# digital-psu.net
KiCad netlist of a schematic drawn in EAGLE
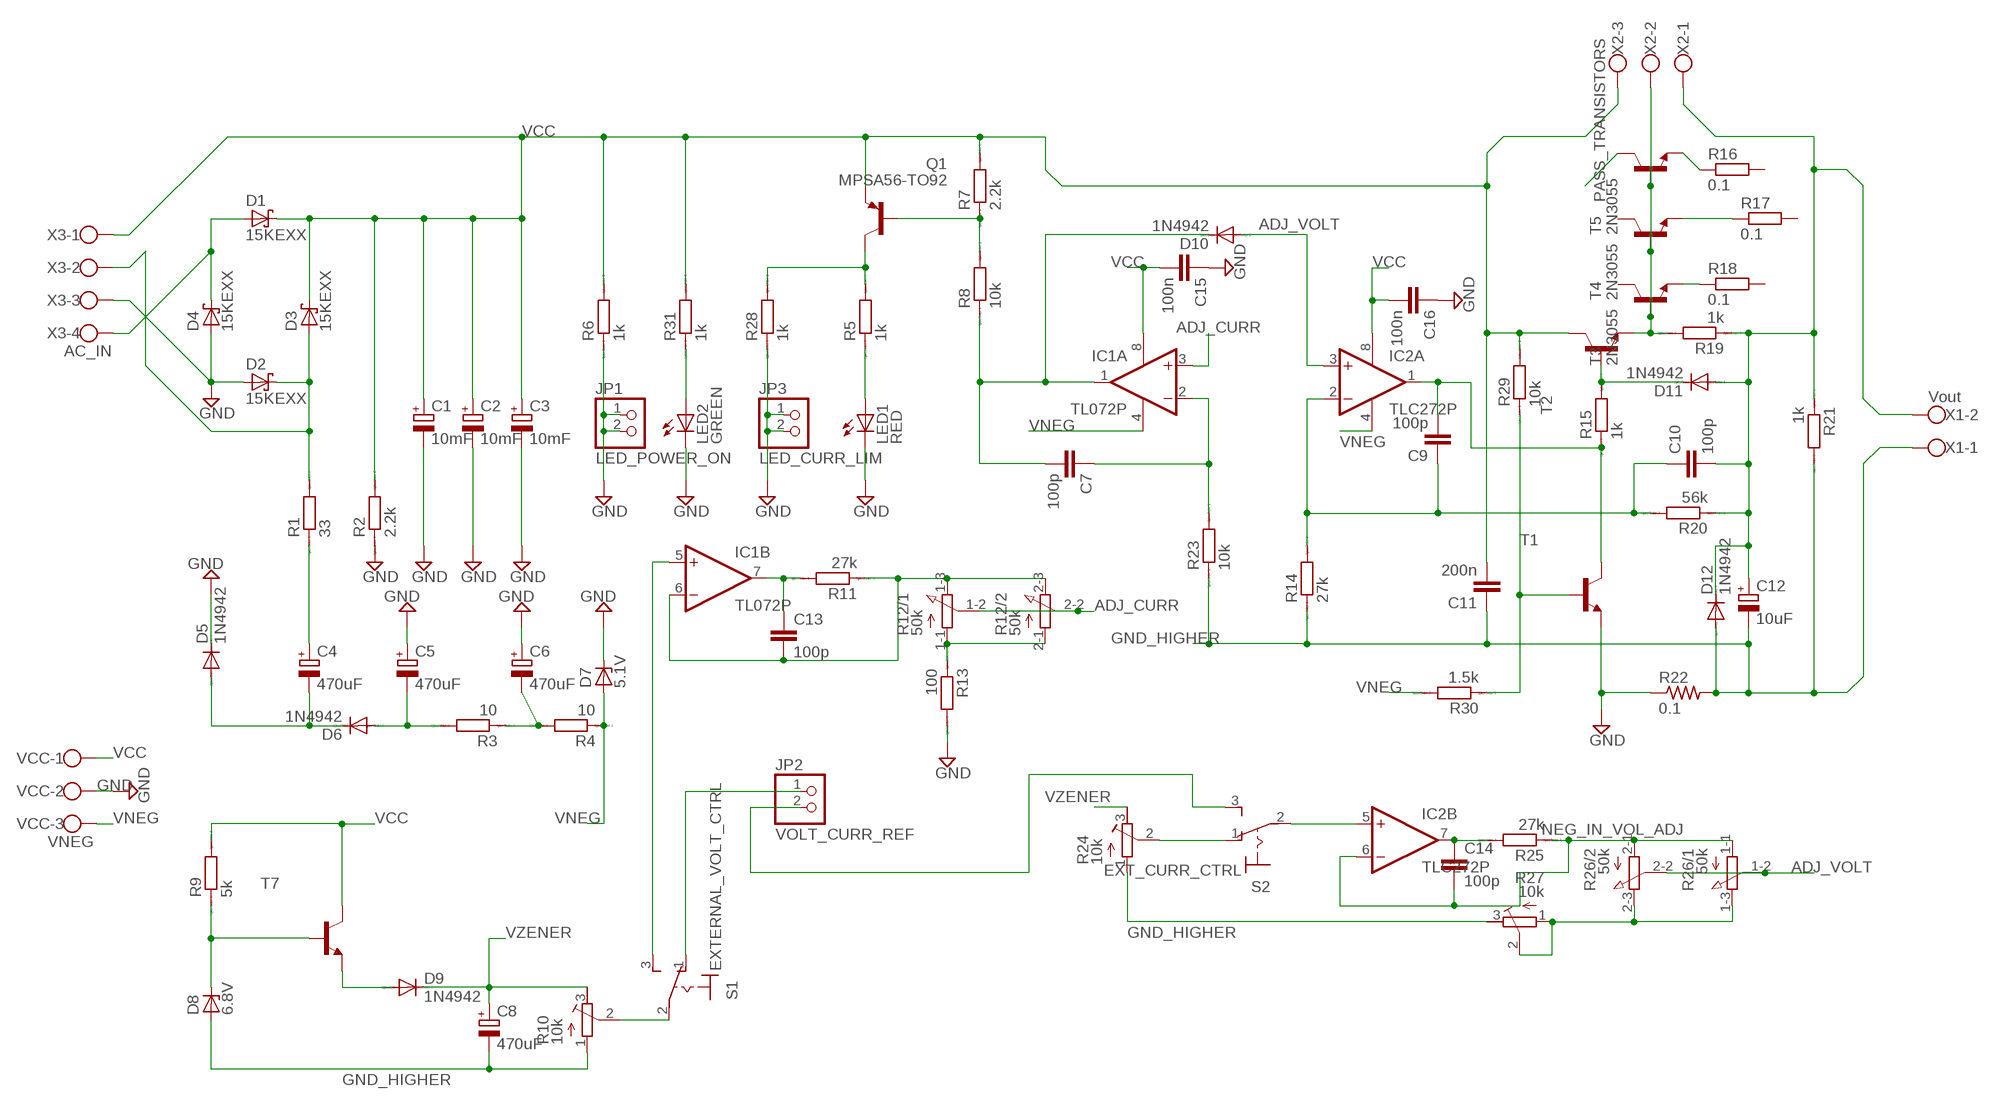
[diagram p0: schematic, sheet 1]

(export (version "E")
  (design (tool "Eeschema 10.0.6"))
  (components
    (comp (ref "C1")
      (value "10mF")
      (footprint "eagle-import:EB22,5D")
      (libsource (lib "eagle-import") (part "CPOL-EUE10-22.5"))
    )
    (comp (ref "C2")
      (value "10mF")
      (footprint "eagle-import:EB22,5D")
      (libsource (lib "eagle-import") (part "CPOL-EUE10-22.5"))
    )
    (comp (ref "C3")
      (value "10mF")
      (footprint "eagle-import:EB22,5D")
      (libsource (lib "eagle-import") (part "CPOL-EUE10-22.5"))
    )
    (comp (ref "C4")
      (value "470uF")
      (footprint "eagle-import:E5-10,5")
      (libsource (lib "eagle-import") (part "CPOL-EUE5-10.5"))
    )
    (comp (ref "C5")
      (value "470uF")
      (footprint "eagle-import:E5-10,5")
      (libsource (lib "eagle-import") (part "CPOL-EUE5-10.5"))
    )
    (comp (ref "C6")
      (value "470uF")
      (footprint "eagle-import:E5-10,5")
      (libsource (lib "eagle-import") (part "CPOL-EUE5-10.5"))
    )
    (comp (ref "C7")
      (value "100p")
      (footprint "eagle-import:C0805")
      (libsource (lib "eagle-import") (part "C-EUC0805"))
    )
    (comp (ref "C8")
      (value "470uF")
      (footprint "eagle-import:E5-10,5")
      (libsource (lib "eagle-import") (part "CPOL-EUE5-10.5"))
    )
    (comp (ref "C9")
      (value "100p")
      (footprint "eagle-import:C0805")
      (libsource (lib "eagle-import") (part "C-EUC0805"))
    )
    (comp (ref "C10")
      (value "100p")
      (footprint "eagle-import:C0805")
      (libsource (lib "eagle-import") (part "C-EUC0805"))
    )
    (comp (ref "C11")
      (value "200n")
      (footprint "eagle-import:C0805")
      (libsource (lib "eagle-import") (part "C-EUC0805"))
    )
    (comp (ref "C12")
      (value "10uF")
      (footprint "eagle-import:E5-10,5")
      (libsource (lib "eagle-import") (part "CPOL-EUE5-10.5"))
    )
    (comp (ref "C13")
      (value "100p")
      (footprint "eagle-import:C0805")
      (libsource (lib "eagle-import") (part "C-EUC0805"))
    )
    (comp (ref "C14")
      (value "100p")
      (footprint "eagle-import:C0805")
      (libsource (lib "eagle-import") (part "C-EUC0805"))
    )
    (comp (ref "C15")
      (value "100n")
      (footprint "eagle-import:C0805")
      (libsource (lib "eagle-import") (part "C-EUC0805"))
    )
    (comp (ref "C16")
      (value "100n")
      (footprint "eagle-import:C0805")
      (libsource (lib "eagle-import") (part "C-EUC0805"))
    )
    (comp (ref "D1")
      (value "15KEXX")
      (footprint "eagle-import:CB429-17")
      (libsource (lib "eagle-import") (part "15KEXX"))
    )
    (comp (ref "D2")
      (value "15KEXX")
      (footprint "eagle-import:CB429-17")
      (libsource (lib "eagle-import") (part "15KEXX"))
    )
    (comp (ref "D3")
      (value "15KEXX")
      (footprint "eagle-import:CB429-17")
      (libsource (lib "eagle-import") (part "15KEXX"))
    )
    (comp (ref "D4")
      (value "15KEXX")
      (footprint "eagle-import:CB429-17")
      (libsource (lib "eagle-import") (part "15KEXX"))
    )
    (comp (ref "D5")
      (value "1N4942")
      (footprint "eagle-import:DO41-10")
      (libsource (lib "eagle-import") (part "1N4942"))
    )
    (comp (ref "D6")
      (value "1N4942")
      (footprint "eagle-import:DO41-10")
      (libsource (lib "eagle-import") (part "1N4942"))
    )
    (comp (ref "D7")
      (value "5.1V")
      (footprint "eagle-import:C1702-15")
      (libsource (lib "eagle-import") (part "ZENER-DIODEC1702-15"))
    )
    (comp (ref "D8")
      (value "6.8V")
      (footprint "eagle-import:C1702-15")
      (libsource (lib "eagle-import") (part "ZENER-DIODEC1702-15"))
    )
    (comp (ref "D9")
      (value "1N4942")
      (footprint "eagle-import:DO41-10")
      (libsource (lib "eagle-import") (part "1N4942"))
    )
    (comp (ref "D10")
      (value "1N4942")
      (footprint "eagle-import:DO41-10")
      (libsource (lib "eagle-import") (part "1N4942"))
    )
    (comp (ref "D11")
      (value "1N4942")
      (footprint "eagle-import:DO41-10")
      (libsource (lib "eagle-import") (part "1N4942"))
    )
    (comp (ref "D12")
      (value "1N4942")
      (footprint "eagle-import:DO41-10")
      (libsource (lib "eagle-import") (part "1N4942"))
    )
    (comp (ref "IC1")
      (value "TL072P")
      (footprint "eagle-import:DIL08")
      (libsource (lib "eagle-import") (part "TL072P"))
    )
    (comp (ref "IC2")
      (value "TLC272P")
      (footprint "eagle-import:DIL08")
      (libsource (lib "eagle-import") (part "TLC272P"))
    )
    (comp (ref "JP1")
      (value "LED_POWER_ON")
      (footprint "eagle-import:1X02")
      (libsource (lib "eagle-import") (part "PINHD-1X2"))
    )
    (comp (ref "JP2")
      (value "VOLT_CURR_REF")
      (footprint "eagle-import:1X02")
      (libsource (lib "eagle-import") (part "PINHD-1X2"))
    )
    (comp (ref "JP3")
      (value "LED_CURR_LIM")
      (footprint "eagle-import:1X02")
      (libsource (lib "eagle-import") (part "PINHD-1X2"))
    )
    (comp (ref "LED1")
      (value "RED")
      (footprint "eagle-import:LED5MM")
      (libsource (lib "eagle-import") (part "LED5MM"))
    )
    (comp (ref "LED2")
      (value "GREEN")
      (footprint "eagle-import:LED5MM")
      (libsource (lib "eagle-import") (part "LED5MM"))
    )
    (comp (ref "Q1")
      (value "MPSA56-TO92")
      (footprint "eagle-import:TO92-CBE")
      (libsource (lib "eagle-import") (part "-?TO92MPSA56"))
    )
    (comp (ref "R1")
      (value "33")
      (footprint "eagle-import:R0805")
      (libsource (lib "eagle-import") (part "R"))
    )
    (comp (ref "R2")
      (value "2.2k")
      (footprint "eagle-import:R0805")
      (libsource (lib "eagle-import") (part "R"))
    )
    (comp (ref "R3")
      (value "10")
      (footprint "eagle-import:R0805")
      (libsource (lib "eagle-import") (part "R"))
    )
    (comp (ref "R4")
      (value "10")
      (footprint "eagle-import:R0805")
      (libsource (lib "eagle-import") (part "R"))
    )
    (comp (ref "R5")
      (value "1k")
      (footprint "eagle-import:R0805")
      (libsource (lib "eagle-import") (part "R"))
    )
    (comp (ref "R6")
      (value "1k")
      (footprint "eagle-import:R0805")
      (libsource (lib "eagle-import") (part "R"))
    )
    (comp (ref "R7")
      (value "2.2k")
      (footprint "eagle-import:R0805")
      (libsource (lib "eagle-import") (part "R"))
    )
    (comp (ref "R8")
      (value "10k")
      (footprint "eagle-import:R0805")
      (libsource (lib "eagle-import") (part "R"))
    )
    (comp (ref "R9")
      (value "5k")
      (footprint "eagle-import:R0805")
      (libsource (lib "eagle-import") (part "R"))
    )
    (comp (ref "R10")
      (value "10k")
      (footprint "eagle-import:RTRIM64W")
      (libsource (lib "eagle-import") (part "R-TRIMM64W"))
    )
    (comp (ref "R11")
      (value "27k")
      (footprint "eagle-import:R0805")
      (libsource (lib "eagle-import") (part "R"))
    )
    (comp (ref "R12")
      (value "50k")
      (footprint "eagle-import:3RP_1610G")
      (libsource (lib "eagle-import") (part "3RP/1610G"))
    )
    (comp (ref "R13")
      (value "100")
      (footprint "eagle-import:R0805")
      (libsource (lib "eagle-import") (part "R"))
    )
    (comp (ref "R14")
      (value "27k")
      (footprint "eagle-import:R0805")
      (libsource (lib "eagle-import") (part "R"))
    )
    (comp (ref "R15")
      (value "1k")
      (footprint "eagle-import:R0805")
      (libsource (lib "eagle-import") (part "R"))
    )
    (comp (ref "R16")
      (value "0.1")
      (footprint "eagle-import:VTA55")
      (libsource (lib "eagle-import") (part "R-EU_VTA55"))
    )
    (comp (ref "R17")
      (value "0.1")
      (footprint "eagle-import:VTA55")
      (libsource (lib "eagle-import") (part "R-EU_VTA55"))
    )
    (comp (ref "R18")
      (value "0.1")
      (footprint "eagle-import:VTA55")
      (libsource (lib "eagle-import") (part "R-EU_VTA55"))
    )
    (comp (ref "R19")
      (value "1k")
      (footprint "eagle-import:R0805")
      (libsource (lib "eagle-import") (part "R"))
    )
    (comp (ref "R20")
      (value "56k")
      (footprint "eagle-import:R0805")
      (libsource (lib "eagle-import") (part "R"))
    )
    (comp (ref "R21")
      (value "1k")
      (footprint "eagle-import:R0805")
      (libsource (lib "eagle-import") (part "R"))
    )
    (comp (ref "R22")
      (value "0.1")
      (footprint "eagle-import:VTA52")
      (libsource (lib "eagle-import") (part "R-US_VTA52"))
    )
    (comp (ref "R23")
      (value "10k")
      (footprint "eagle-import:R0805")
      (libsource (lib "eagle-import") (part "R"))
    )
    (comp (ref "R24")
      (value "10k")
      (footprint "eagle-import:RTRIM64W")
      (libsource (lib "eagle-import") (part "R-TRIMM64W"))
    )
    (comp (ref "R25")
      (value "27k")
      (footprint "eagle-import:R0805")
      (libsource (lib "eagle-import") (part "R"))
    )
    (comp (ref "R26")
      (value "50k")
      (footprint "eagle-import:3RP_1610G")
      (libsource (lib "eagle-import") (part "3RP/1610G"))
    )
    (comp (ref "R27")
      (value "10k")
      (footprint "eagle-import:RTRIM64W")
      (libsource (lib "eagle-import") (part "R-TRIMM64W"))
    )
    (comp (ref "R28")
      (value "1k")
      (footprint "eagle-import:R0805")
      (libsource (lib "eagle-import") (part "R"))
    )
    (comp (ref "R29")
      (value "10k")
      (footprint "eagle-import:R0805")
      (libsource (lib "eagle-import") (part "R"))
    )
    (comp (ref "R30")
      (value "1.5k")
      (footprint "eagle-import:R0805")
      (libsource (lib "eagle-import") (part "R"))
    )
    (comp (ref "R31")
      (value "1k")
      (footprint "eagle-import:R0805")
      (libsource (lib "eagle-import") (part "R"))
    )
    (comp (ref "S1")
      (value "EXTERNAL_VOLT_CTRL")
      (footprint "eagle-import:320-916")
      (libsource (lib "eagle-import") (part "320-916"))
    )
    (comp (ref "S2")
      (value "EXT_CURR_CTRL")
      (footprint "eagle-import:320-916")
      (libsource (lib "eagle-import") (part "320-916"))
    )
    (comp (ref "T1")
      (value "-NPN-TO92-EBC")
      (footprint "eagle-import:TO92-EBC")
      (libsource (lib "eagle-import") (part "-NPN-TO92-EBC"))
    )
    (comp (ref "T2")
      (value "-NPN-TO92-EBC")
      (footprint "eagle-import:TO92-EBC")
      (libsource (lib "eagle-import") (part "-NPN-TO92-EBC"))
    )
    (comp (ref "T3")
      (value "2N3055")
      (footprint "eagle-import:TO3")
      (libsource (lib "eagle-import") (part "-NPN-TO3/"))
    )
    (comp (ref "T4")
      (value "2N3055")
      (footprint "eagle-import:TO3")
      (libsource (lib "eagle-import") (part "-NPN-TO3/"))
    )
    (comp (ref "T5")
      (value "2N3055")
      (footprint "eagle-import:TO3")
      (libsource (lib "eagle-import") (part "-NPN-TO3/"))
    )
    (comp (ref "T7")
      (value "-NPN-TO92-EBC")
      (footprint "eagle-import:TO92-EBC")
      (libsource (lib "eagle-import") (part "-NPN-TO92-EBC"))
    )
    (comp (ref "VCC")
      (value "VNEG")
      (footprint "eagle-import:W237-103")
      (fields (field (name "MPN") "237-103"))
      (libsource (lib "eagle-import") (part "W237-103"))
    )
    (comp (ref "X1")
      (value "Vout")
      (footprint "eagle-import:W237-113")
      (libsource (lib "eagle-import") (part "W237-113"))
    )
    (comp (ref "X2")
      (value "PASS_TRANSISTORS")
      (footprint "eagle-import:W237-103")
      (fields (field (name "MPN") "237-103"))
      (libsource (lib "eagle-import") (part "W237-103"))
    )
    (comp (ref "X3")
      (value "AC_IN")
      (footprint "eagle-import:W237-4")
      (libsource (lib "eagle-import") (part "W237-4"))
    )
  )
  (nets
    (net (code "1") (name "/ADJ_CURR") (class "Default")
      (node (ref "IC1") (pin "3") (pinfunction "+IN_3") (pintype "input"))
      (node (ref "R12") (pin "1-2") (pinfunction "S_1-2") (pintype "passive"))
      (node (ref "R12") (pin "2-2") (pinfunction "S_2-2") (pintype "passive"))
    )
    (net (code "2") (name "/ADJ_VOLT") (class "Default")
      (node (ref "D10") (pin "A") (pinfunction "A_A") (pintype "passive"))
      (node (ref "IC2") (pin "3") (pinfunction "+IN_3") (pintype "input"))
      (node (ref "R26") (pin "1-2") (pinfunction "S_1-2") (pintype "passive"))
      (node (ref "R26") (pin "2-2") (pinfunction "S_2-2") (pintype "passive"))
    )
    (net (code "3") (name "/GND_HIGHER") (class "Default")
      (node (ref "C11") (pin "1") (pinfunction "1_1") (pintype "passive"))
      (node (ref "C12") (pin "-") (pinfunction "-_-") (pintype "passive"))
      (node (ref "C8") (pin "-") (pinfunction "-_-") (pintype "passive"))
      (node (ref "D12") (pin "A") (pinfunction "A_A") (pintype "passive"))
      (node (ref "D8") (pin "A") (pinfunction "A_A") (pintype "passive"))
      (node (ref "R10") (pin "1") (pinfunction "A_1") (pintype "passive"))
      (node (ref "R14") (pin "1") (pinfunction "1_1") (pintype "passive"))
      (node (ref "R21") (pin "2") (pinfunction "2_2") (pintype "passive"))
      (node (ref "R22") (pin "2") (pinfunction "2_2") (pintype "passive"))
      (node (ref "R23") (pin "1") (pinfunction "1_1") (pintype "passive"))
      (node (ref "R24") (pin "1") (pinfunction "A_1") (pintype "passive"))
      (node (ref "R27") (pin "3") (pinfunction "E_3") (pintype "passive"))
      (node (ref "X1") (pin "1") (pinfunction "KL_1") (pintype "passive"))
    )
    (net (code "4") (name "/NEG_IN_VOL_ADJ") (class "Default")
      (node (ref "C14") (pin "2") (pinfunction "2_2") (pintype "passive"))
      (node (ref "IC2") (pin "6") (pinfunction "-IN_6") (pintype "input"))
      (node (ref "R25") (pin "1") (pinfunction "1_1") (pintype "passive"))
      (node (ref "R26") (pin "1-1") (pinfunction "A_1-1") (pintype "passive"))
      (node (ref "R26") (pin "2-1") (pinfunction "A_2-1") (pintype "passive"))
    )
    (net (code "5") (name "/VCC") (class "Default")
      (node (ref "C1") (pin "+") (pinfunction "+_+") (pintype "passive"))
      (node (ref "C11") (pin "2") (pinfunction "2_2") (pintype "passive"))
      (node (ref "C15") (pin "2") (pinfunction "2_2") (pintype "passive"))
      (node (ref "C16") (pin "2") (pinfunction "2_2") (pintype "passive"))
      (node (ref "C2") (pin "+") (pinfunction "+_+") (pintype "passive"))
      (node (ref "C3") (pin "+") (pinfunction "+_+") (pintype "passive"))
      (node (ref "D1") (pin "C") (pinfunction "C_C") (pintype "passive"))
      (node (ref "D3") (pin "C") (pinfunction "C_C") (pintype "passive"))
      (node (ref "IC1") (pin "8") (pinfunction "V+_8") (pintype "power_in"))
      (node (ref "IC2") (pin "8") (pinfunction "V+_8") (pintype "power_in"))
      (node (ref "Q1") (pin "E") (pinfunction "E_E") (pintype "passive"))
      (node (ref "R2") (pin "2") (pinfunction "2_2") (pintype "passive"))
      (node (ref "R29") (pin "2") (pinfunction "2_2") (pintype "passive"))
      (node (ref "R31") (pin "2") (pinfunction "2_2") (pintype "passive"))
      (node (ref "R6") (pin "2") (pinfunction "2_2") (pintype "passive"))
      (node (ref "R7") (pin "2") (pinfunction "2_2") (pintype "passive"))
      (node (ref "R9") (pin "2") (pinfunction "2_2") (pintype "passive"))
      (node (ref "T2") (pin "C") (pinfunction "C_C") (pintype "passive"))
      (node (ref "T7") (pin "C") (pinfunction "C_C") (pintype "passive"))
      (node (ref "VCC") (pin "1") (pinfunction "KL_1") (pintype "passive"))
      (node (ref "X2") (pin "3") (pinfunction "KL_3") (pintype "passive"))
      (node (ref "X3") (pin "1") (pinfunction "KL_1") (pintype "passive"))
    )
    (net (code "6") (name "/VNEG") (class "Default")
      (node (ref "D7") (pin "A") (pinfunction "A_A") (pintype "passive"))
      (node (ref "IC1") (pin "4") (pinfunction "V-_4") (pintype "power_in"))
      (node (ref "IC2") (pin "4") (pinfunction "V-_4") (pintype "power_in"))
      (node (ref "R30") (pin "2") (pinfunction "2_2") (pintype "passive"))
      (node (ref "R4") (pin "1") (pinfunction "1_1") (pintype "passive"))
      (node (ref "VCC") (pin "3") (pinfunction "KL_3") (pintype "passive"))
    )
    (net (code "7") (name "/VZENER") (class "Default")
      (node (ref "C8") (pin "+") (pinfunction "+_+") (pintype "passive"))
      (node (ref "D9") (pin "C") (pinfunction "C_C") (pintype "passive"))
      (node (ref "R10") (pin "3") (pinfunction "E_3") (pintype "passive"))
      (node (ref "R24") (pin "3") (pinfunction "E_3") (pintype "passive"))
    )
    (net (code "8") (name "GND") (class "Default")
      (node (ref "C1") (pin "-") (pinfunction "-_-") (pintype "passive"))
      (node (ref "C15") (pin "1") (pinfunction "1_1") (pintype "passive"))
      (node (ref "C16") (pin "1") (pinfunction "1_1") (pintype "passive"))
      (node (ref "C2") (pin "-") (pinfunction "-_-") (pintype "passive"))
      (node (ref "C3") (pin "-") (pinfunction "-_-") (pintype "passive"))
      (node (ref "C5") (pin "+") (pinfunction "+_+") (pintype "passive"))
      (node (ref "C6") (pin "+") (pinfunction "+_+") (pintype "passive"))
      (node (ref "D2") (pin "A") (pinfunction "A_A") (pintype "passive"))
      (node (ref "D4") (pin "A") (pinfunction "A_A") (pintype "passive"))
      (node (ref "D5") (pin "C") (pinfunction "C_C") (pintype "passive"))
      (node (ref "D7") (pin "C") (pinfunction "C_C") (pintype "passive"))
      (node (ref "JP1") (pin "1") (pinfunction "1_1") (pintype "passive"))
      (node (ref "JP1") (pin "2") (pinfunction "2_2") (pintype "passive"))
      (node (ref "JP3") (pin "1") (pinfunction "1_1") (pintype "passive"))
      (node (ref "JP3") (pin "2") (pinfunction "2_2") (pintype "passive"))
      (node (ref "LED1") (pin "K") (pinfunction "C_K") (pintype "passive"))
      (node (ref "LED2") (pin "K") (pinfunction "C_K") (pintype "passive"))
      (node (ref "R13") (pin "2") (pinfunction "2_2") (pintype "passive"))
      (node (ref "R2") (pin "1") (pinfunction "1_1") (pintype "passive"))
      (node (ref "R22") (pin "1") (pinfunction "1_1") (pintype "passive"))
      (node (ref "R28") (pin "1") (pinfunction "1_1") (pintype "passive"))
      (node (ref "R6") (pin "1") (pinfunction "1_1") (pintype "passive"))
      (node (ref "T1") (pin "E") (pinfunction "E_E") (pintype "passive"))
      (node (ref "VCC") (pin "2") (pinfunction "KL_2") (pintype "passive"))
      (node (ref "X3") (pin "3") (pinfunction "KL_3") (pintype "passive"))
    )
    (net (code "9") (name "Net-(C4-Pad+)") (class "Default")
      (node (ref "C4") (pin "+") (pinfunction "+_+") (pintype "passive"))
      (node (ref "R1") (pin "1") (pinfunction "1_1") (pintype "passive"))
    )
    (net (code "10") (name "Net-(C4-Pad-)") (class "Default")
      (node (ref "C4") (pin "-") (pinfunction "-_-") (pintype "passive"))
      (node (ref "D5") (pin "A") (pinfunction "A_A") (pintype "passive"))
      (node (ref "D6") (pin "C") (pinfunction "C_C") (pintype "passive"))
    )
    (net (code "11") (name "Net-(C5-Pad-)") (class "Default")
      (node (ref "C5") (pin "-") (pinfunction "-_-") (pintype "passive"))
      (node (ref "D6") (pin "A") (pinfunction "A_A") (pintype "passive"))
      (node (ref "R3") (pin "2") (pinfunction "2_2") (pintype "passive"))
    )
    (net (code "12") (name "Net-(C6-Pad-)") (class "Default")
      (node (ref "C6") (pin "-") (pinfunction "-_-") (pintype "passive"))
      (node (ref "R3") (pin "1") (pinfunction "1_1") (pintype "passive"))
      (node (ref "R4") (pin "2") (pinfunction "2_2") (pintype "passive"))
    )
    (net (code "13") (name "Net-(D8-PadC)") (class "Default")
      (node (ref "D8") (pin "C") (pinfunction "C_C") (pintype "passive"))
      (node (ref "R9") (pin "1") (pinfunction "1_1") (pintype "passive"))
      (node (ref "T7") (pin "B") (pinfunction "B_B") (pintype "passive"))
    )
    (net (code "14") (name "Net-(D9-PadA)") (class "Default")
      (node (ref "D9") (pin "A") (pinfunction "A_A") (pintype "passive"))
      (node (ref "T7") (pin "E") (pinfunction "E_E") (pintype "passive"))
    )
    (net (code "15") (name "Net-(D11-PadC)") (class "Default")
      (node (ref "D11") (pin "C") (pinfunction "C_C") (pintype "passive"))
      (node (ref "R15") (pin "2") (pinfunction "2_2") (pintype "passive"))
      (node (ref "T2") (pin "B") (pinfunction "B_B") (pintype "passive"))
    )
    (net (code "16") (name "Net-(IC1A--IN)") (class "Default")
      (node (ref "C7") (pin "1") (pinfunction "1_1") (pintype "passive"))
      (node (ref "IC1") (pin "2") (pinfunction "-IN_2") (pintype "input"))
      (node (ref "R23") (pin "2") (pinfunction "2_2") (pintype "passive"))
    )
    (net (code "17") (name "Net-(IC1A-OUT)") (class "Default")
      (node (ref "C7") (pin "2") (pinfunction "2_2") (pintype "passive"))
      (node (ref "D10") (pin "C") (pinfunction "C_C") (pintype "passive"))
      (node (ref "IC1") (pin "1") (pinfunction "OUT_1") (pintype "output"))
      (node (ref "R8") (pin "1") (pinfunction "1_1") (pintype "passive"))
    )
    (net (code "18") (name "Net-(IC1B-+IN)") (class "Default")
      (node (ref "IC1") (pin "5") (pinfunction "+IN_5") (pintype "input"))
      (node (ref "S1") (pin "3") (pinfunction "S_3") (pintype "passive"))
    )
    (net (code "19") (name "Net-(IC1B--IN)") (class "Default")
      (node (ref "C13") (pin "2") (pinfunction "2_2") (pintype "passive"))
      (node (ref "IC1") (pin "6") (pinfunction "-IN_6") (pintype "input"))
      (node (ref "R11") (pin "1") (pinfunction "1_1") (pintype "passive"))
      (node (ref "R12") (pin "1-3") (pinfunction "E_1-3") (pintype "passive"))
      (node (ref "R12") (pin "2-3") (pinfunction "E_2-3") (pintype "passive"))
    )
    (net (code "20") (name "Net-(IC1B-OUT)") (class "Default")
      (node (ref "C13") (pin "1") (pinfunction "1_1") (pintype "passive"))
      (node (ref "IC1") (pin "7") (pinfunction "OUT_7") (pintype "output"))
      (node (ref "R11") (pin "2") (pinfunction "2_2") (pintype "passive"))
    )
    (net (code "21") (name "Net-(IC2A--IN)") (class "Default")
      (node (ref "C10") (pin "1") (pinfunction "1_1") (pintype "passive"))
      (node (ref "C9") (pin "1") (pinfunction "1_1") (pintype "passive"))
      (node (ref "IC2") (pin "2") (pinfunction "-IN_2") (pintype "input"))
      (node (ref "R14") (pin "2") (pinfunction "2_2") (pintype "passive"))
      (node (ref "R20") (pin "2") (pinfunction "2_2") (pintype "passive"))
    )
    (net (code "22") (name "Net-(IC2A-OUT)") (class "Default")
      (node (ref "C9") (pin "2") (pinfunction "2_2") (pintype "passive"))
      (node (ref "IC2") (pin "1") (pinfunction "OUT_1") (pintype "output"))
      (node (ref "R15") (pin "1") (pinfunction "1_1") (pintype "passive"))
      (node (ref "T1") (pin "C") (pinfunction "C_C") (pintype "passive"))
    )
    (net (code "23") (name "Net-(IC2B-+IN)") (class "Default")
      (node (ref "IC2") (pin "5") (pinfunction "+IN_5") (pintype "input"))
      (node (ref "S2") (pin "2") (pinfunction "P_2") (pintype "passive"))
    )
    (net (code "24") (name "Net-(IC2B-OUT)") (class "Default")
      (node (ref "C14") (pin "1") (pinfunction "1_1") (pintype "passive"))
      (node (ref "IC2") (pin "7") (pinfunction "OUT_7") (pintype "output"))
      (node (ref "R25") (pin "2") (pinfunction "2_2") (pintype "passive"))
    )
    (net (code "25") (name "Net-(LED1-PadA)") (class "Default")
      (node (ref "LED1") (pin "A") (pinfunction "A_A") (pintype "passive"))
      (node (ref "R5") (pin "1") (pinfunction "1_1") (pintype "passive"))
    )
    (net (code "26") (name "Net-(LED2-PadA)") (class "Default")
      (node (ref "LED2") (pin "A") (pinfunction "A_A") (pintype "passive"))
      (node (ref "R31") (pin "1") (pinfunction "1_1") (pintype "passive"))
    )
    (net (code "27") (name "Net-(Q1-PadB)") (class "Default")
      (node (ref "Q1") (pin "B") (pinfunction "B_B") (pintype "passive"))
      (node (ref "R7") (pin "1") (pinfunction "1_1") (pintype "passive"))
      (node (ref "R8") (pin "2") (pinfunction "2_2") (pintype "passive"))
    )
    (net (code "28") (name "Net-(Q1-PadC)") (class "Default")
      (node (ref "Q1") (pin "C") (pinfunction "C_C") (pintype "passive"))
      (node (ref "R28") (pin "2") (pinfunction "2_2") (pintype "passive"))
      (node (ref "R5") (pin "2") (pinfunction "2_2") (pintype "passive"))
    )
    (net (code "29") (name "Net-(R10-S)") (class "Default")
      (node (ref "R10") (pin "2") (pinfunction "S_2") (pintype "passive"))
      (node (ref "S1") (pin "2") (pinfunction "P_2") (pintype "passive"))
    )
    (net (code "30") (name "Net-(R12A-A)") (class "Default")
      (node (ref "R12") (pin "1-1") (pinfunction "A_1-1") (pintype "passive"))
      (node (ref "R12") (pin "2-1") (pinfunction "A_2-1") (pintype "passive"))
      (node (ref "R13") (pin "1") (pinfunction "1_1") (pintype "passive"))
    )
    (net (code "31") (name "Net-(R16-Pad1)") (class "Default")
      (node (ref "R16") (pin "1") (pinfunction "1_1") (pintype "passive"))
      (node (ref "T5") (pin "E") (pinfunction "E_E") (pintype "passive"))
    )
    (net (code "32") (name "Net-(R17-Pad1)") (class "Default")
      (node (ref "R17") (pin "1") (pinfunction "1_1") (pintype "passive"))
      (node (ref "T4") (pin "E") (pinfunction "E_E") (pintype "passive"))
    )
    (net (code "33") (name "Net-(R18-Pad1)") (class "Default")
      (node (ref "R18") (pin "1") (pinfunction "1_1") (pintype "passive"))
      (node (ref "T3") (pin "E") (pinfunction "E_E") (pintype "passive"))
    )
    (net (code "34") (name "Net-(R24-S)") (class "Default")
      (node (ref "R24") (pin "2") (pinfunction "S_2") (pintype "passive"))
      (node (ref "S2") (pin "1") (pinfunction "O_1") (pintype "passive"))
    )
    (net (code "35") (name "Net-(R26A-E)") (class "Default")
      (node (ref "R26") (pin "1-3") (pinfunction "E_1-3") (pintype "passive"))
      (node (ref "R26") (pin "2-3") (pinfunction "E_2-3") (pintype "passive"))
      (node (ref "R27") (pin "1") (pinfunction "A_1") (pintype "passive"))
      (node (ref "R27") (pin "2") (pinfunction "S_2") (pintype "passive"))
    )
    (net (code "36") (name "Net-(R29-Pad1)") (class "Default")
      (node (ref "R29") (pin "1") (pinfunction "1_1") (pintype "passive"))
      (node (ref "R30") (pin "1") (pinfunction "1_1") (pintype "passive"))
      (node (ref "T1") (pin "B") (pinfunction "B_B") (pintype "passive"))
    )
    (net (code "37") (name "Net-(S1-O)") (class "Default")
      (node (ref "JP2") (pin "1") (pinfunction "1_1") (pintype "passive"))
      (node (ref "S1") (pin "1") (pinfunction "O_1") (pintype "passive"))
    )
    (net (code "38") (name "Net-(S2-S)") (class "Default")
      (node (ref "JP2") (pin "2") (pinfunction "2_2") (pintype "passive"))
      (node (ref "S2") (pin "3") (pinfunction "S_3") (pintype "passive"))
    )
    (net (code "39") (name "Net-(X1B-KL)") (class "Default")
      (node (ref "C10") (pin "2") (pinfunction "2_2") (pintype "passive"))
      (node (ref "C12") (pin "+") (pinfunction "+_+") (pintype "passive"))
      (node (ref "D11") (pin "A") (pinfunction "A_A") (pintype "passive"))
      (node (ref "D12") (pin "C") (pinfunction "C_C") (pintype "passive"))
      (node (ref "R19") (pin "1") (pinfunction "1_1") (pintype "passive"))
      (node (ref "R20") (pin "1") (pinfunction "1_1") (pintype "passive"))
      (node (ref "R21") (pin "1") (pinfunction "1_1") (pintype "passive"))
      (node (ref "X1") (pin "2") (pinfunction "KL_2") (pintype "passive"))
      (node (ref "X2") (pin "1") (pinfunction "KL_1") (pintype "passive"))
    )
    (net (code "40") (name "Net-(X2B-KL)") (class "Default")
      (node (ref "R19") (pin "2") (pinfunction "2_2") (pintype "passive"))
      (node (ref "T2") (pin "E") (pinfunction "E_E") (pintype "passive"))
      (node (ref "T3") (pin "B") (pinfunction "B_B") (pintype "passive"))
      (node (ref "T4") (pin "B") (pinfunction "B_B") (pintype "passive"))
      (node (ref "T5") (pin "B") (pinfunction "B_B") (pintype "passive"))
      (node (ref "X2") (pin "2") (pinfunction "KL_2") (pintype "passive"))
    )
    (net (code "41") (name "Net-(X3B-KL)") (class "Default")
      (node (ref "D2") (pin "C") (pinfunction "C_C") (pintype "passive"))
      (node (ref "D3") (pin "A") (pinfunction "A_A") (pintype "passive"))
      (node (ref "R1") (pin "2") (pinfunction "2_2") (pintype "passive"))
      (node (ref "X3") (pin "2") (pinfunction "KL_2") (pintype "passive"))
    )
    (net (code "42") (name "Net-(X3D-KL)") (class "Default")
      (node (ref "D1") (pin "A") (pinfunction "A_A") (pintype "passive"))
      (node (ref "D4") (pin "C") (pinfunction "C_C") (pintype "passive"))
      (node (ref "X3") (pin "4") (pinfunction "KL_4") (pintype "passive"))
    )
    (net (code "43") (name "unconnected-(R16-Pad2)") (class "Default")
      (node (ref "R16") (pin "2") (pinfunction "2_2") (pintype "passive"))
    )
    (net (code "44") (name "unconnected-(R17-Pad2)") (class "Default")
      (node (ref "R17") (pin "2") (pinfunction "2_2") (pintype "passive"))
    )
    (net (code "45") (name "unconnected-(R18-Pad2)") (class "Default")
      (node (ref "R18") (pin "2") (pinfunction "2_2") (pintype "passive"))
    )
    (net (code "46") (name "unconnected-(T3-PadC)") (class "Default")
      (node (ref "T3") (pin "C") (pinfunction "C_C") (pintype "passive"))
    )
    (net (code "47") (name "unconnected-(T4-PadC)") (class "Default")
      (node (ref "T4") (pin "C") (pinfunction "C_C") (pintype "passive"))
    )
    (net (code "48") (name "unconnected-(T5-PadC)") (class "Default")
      (node (ref "T5") (pin "C") (pinfunction "C_C") (pintype "passive"))
    )
  )
)
